# Ardumouse_test.net
KiCad netlist of a schematic drawn in EAGLE
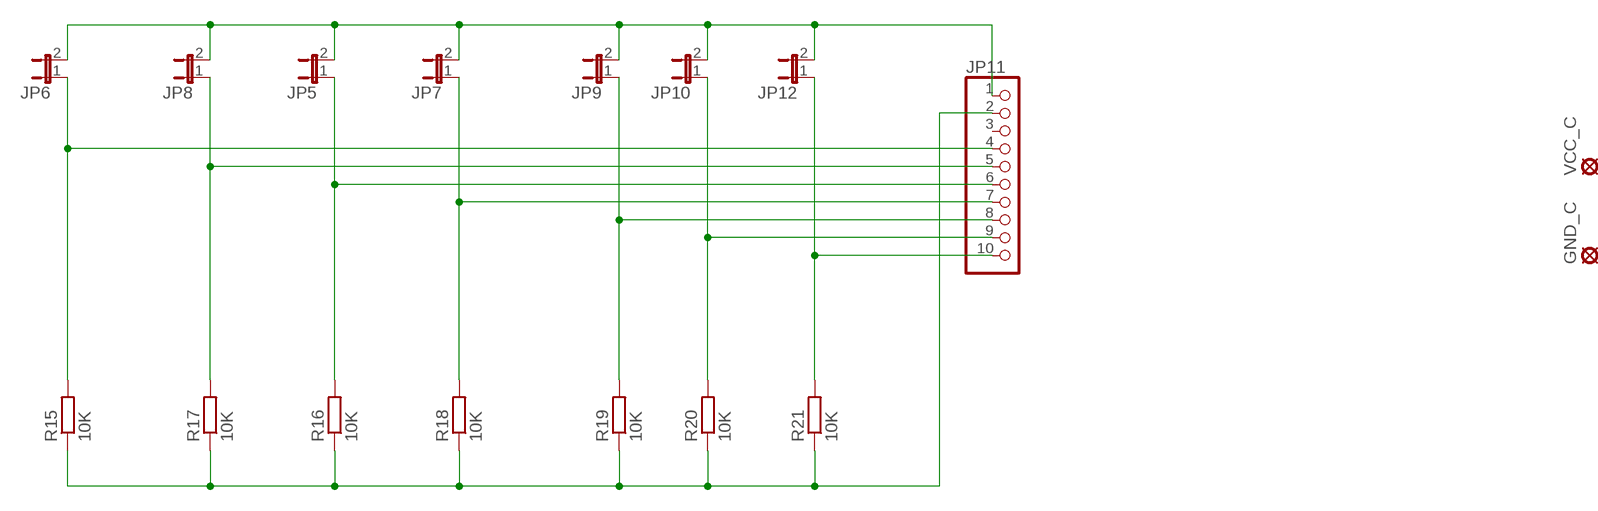
[diagram p0: schematic, sheet 1, part 1 of 2]
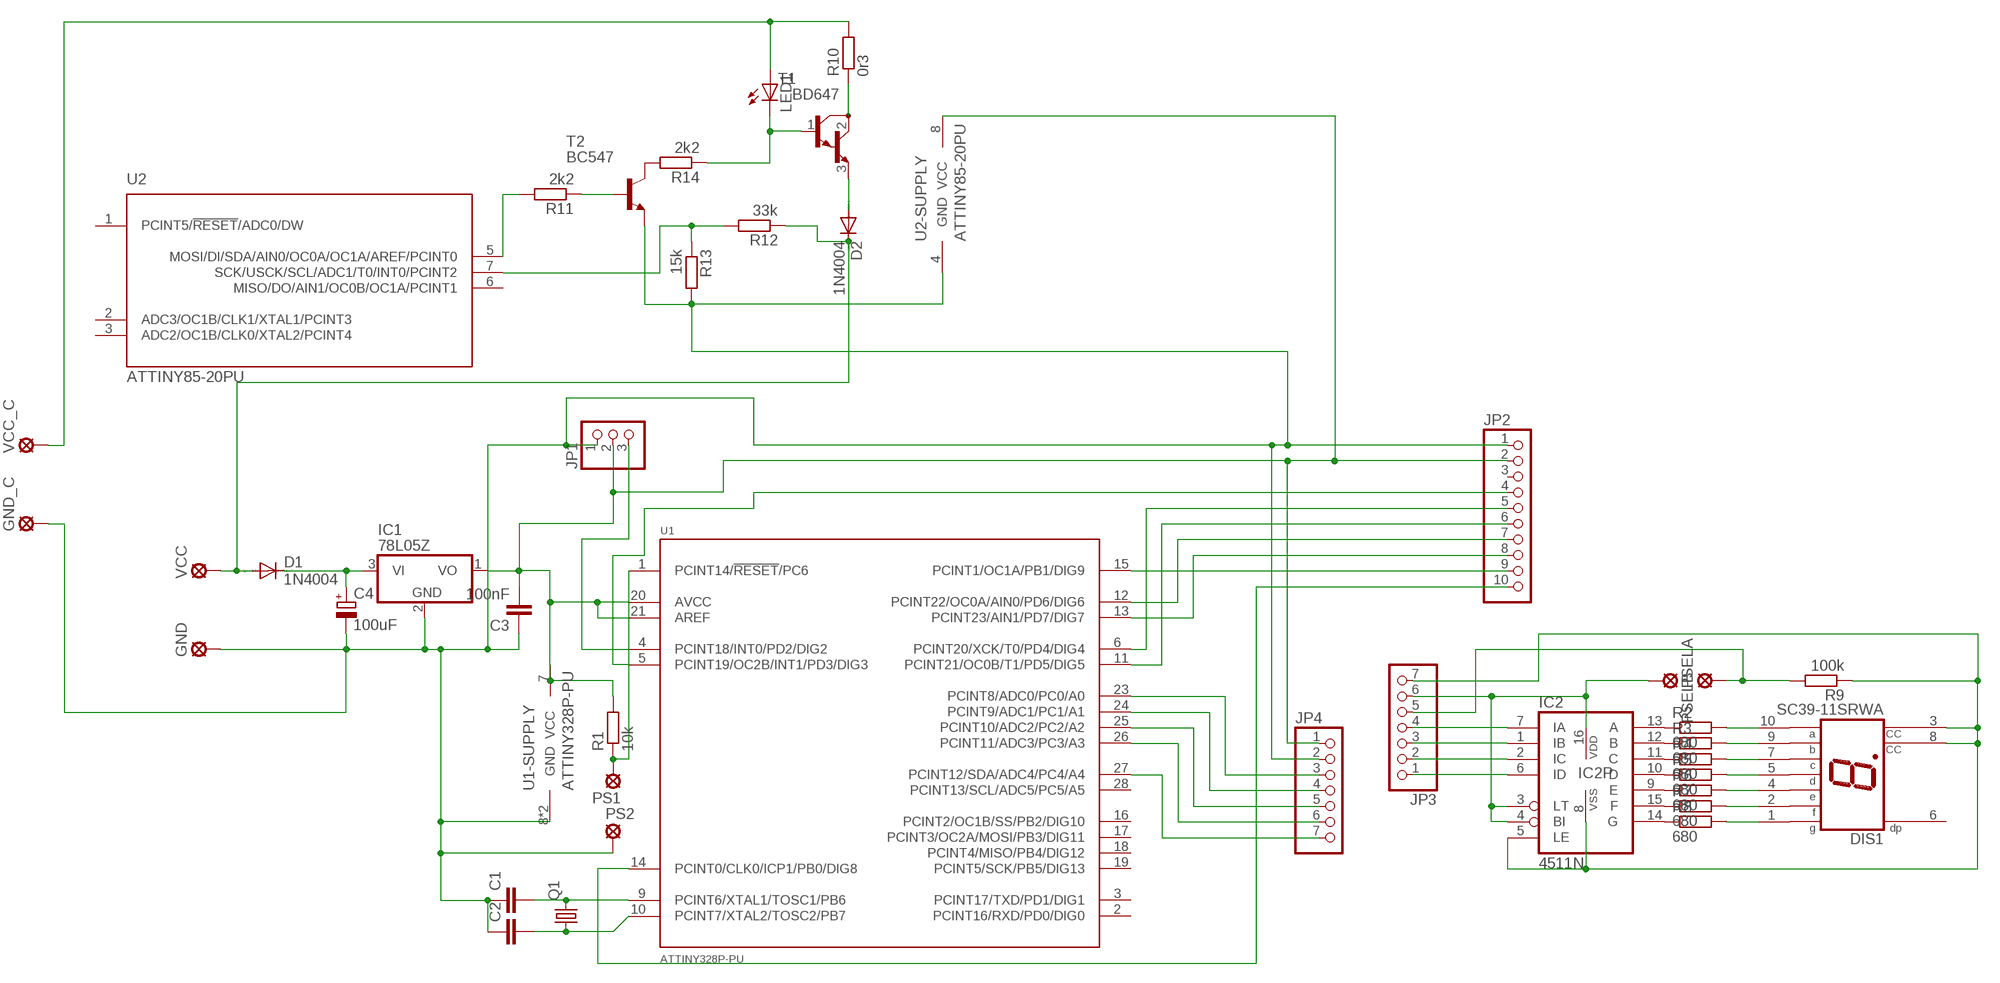
[diagram p1: schematic, sheet 1, part 2 of 2]

(export (version "E")
  (design (tool "Eeschema 10.0.6"))
  (components
    (comp (ref "C1")
      (value "C2,5-3")
      (footprint "eagle-import:C2.5-3")
      (libsource (lib "eagle-import") (part "C2,5-3"))
    )
    (comp (ref "C2")
      (value "C2,5-3")
      (footprint "eagle-import:C2.5-3")
      (libsource (lib "eagle-import") (part "C2,5-3"))
    )
    (comp (ref "C3")
      (value "100nF")
      (footprint "eagle-import:C2.5-3")
      (libsource (lib "eagle-import") (part "C2,5-3"))
    )
    (comp (ref "C4")
      (value "100uF")
      (footprint "eagle-import:E3,5-8")
      (libsource (lib "eagle-import") (part "CPOL-EUE3.5-8"))
    )
    (comp (ref "D1")
      (value "1N4004")
      (footprint "eagle-import:DO41-10")
      (libsource (lib "eagle-import") (part "1N4004"))
    )
    (comp (ref "D2")
      (value "1N4004")
      (footprint "eagle-import:DO41-10")
      (libsource (lib "eagle-import") (part "1N4004"))
    )
    (comp (ref "DIS1")
      (value "SC39-11SRWA")
      (footprint "eagle-import:HDSP-E")
      (libsource (lib "eagle-import") (part "SC39-11SRWA"))
    )
    (comp (ref "GND")
      (value "LSP10")
      (footprint "eagle-import:LSP10")
      (libsource (lib "eagle-import") (part "LSP10"))
    )
    (comp (ref "GND_C")
      (value "LSP10")
      (footprint "eagle-import:LSP10")
      (libsource (lib "eagle-import") (part "LSP10"))
    )
    (comp (ref "IC1")
      (value "78L05Z")
      (footprint "eagle-import:TO92")
      (libsource (lib "eagle-import") (part "78ZL05"))
    )
    (comp (ref "IC2")
      (value "4511N")
      (footprint "eagle-import:DIL16")
      (libsource (lib "eagle-import") (part "4511N"))
    )
    (comp (ref "JP1")
      (value "PINHD-1X3")
      (footprint "eagle-import:1X03")
      (libsource (lib "eagle-import") (part "PINHD-1X3"))
    )
    (comp (ref "JP2")
      (value "PINHD-1X10")
      (footprint "eagle-import:1X10")
      (libsource (lib "eagle-import") (part "PINHD-1X10"))
    )
    (comp (ref "JP3")
      (value "PINHD-1X7")
      (footprint "eagle-import:1X07")
      (libsource (lib "eagle-import") (part "PINHD-1X7"))
    )
    (comp (ref "JP4")
      (value "PINHD-1X7")
      (footprint "eagle-import:1X07")
      (libsource (lib "eagle-import") (part "PINHD-1X7"))
    )
    (comp (ref "JP5")
      (value "JP1E")
      (footprint "eagle-import:JP1")
      (libsource (lib "eagle-import") (part "JP1E"))
    )
    (comp (ref "JP6")
      (value "JP1E")
      (footprint "eagle-import:JP1")
      (libsource (lib "eagle-import") (part "JP1E"))
    )
    (comp (ref "JP7")
      (value "JP1E")
      (footprint "eagle-import:JP1")
      (libsource (lib "eagle-import") (part "JP1E"))
    )
    (comp (ref "JP8")
      (value "JP1E")
      (footprint "eagle-import:JP1")
      (libsource (lib "eagle-import") (part "JP1E"))
    )
    (comp (ref "JP9")
      (value "JP1E")
      (footprint "eagle-import:JP1")
      (libsource (lib "eagle-import") (part "JP1E"))
    )
    (comp (ref "JP10")
      (value "JP1E")
      (footprint "eagle-import:JP1")
      (libsource (lib "eagle-import") (part "JP1E"))
    )
    (comp (ref "JP11")
      (value "PINHD-1X10")
      (footprint "eagle-import:1X10")
      (libsource (lib "eagle-import") (part "PINHD-1X10"))
    )
    (comp (ref "JP12")
      (value "JP1E")
      (footprint "eagle-import:JP1")
      (libsource (lib "eagle-import") (part "JP1E"))
    )
    (comp (ref "LED1")
      (value "LED5MM")
      (footprint "eagle-import:LED5MM")
      (libsource (lib "eagle-import") (part "LED5MM"))
    )
    (comp (ref "PS1")
      (value "LSP10")
      (footprint "eagle-import:LSP10")
      (libsource (lib "eagle-import") (part "LSP10"))
    )
    (comp (ref "PS2")
      (value "LSP10")
      (footprint "eagle-import:LSP10")
      (libsource (lib "eagle-import") (part "LSP10"))
    )
    (comp (ref "PSELA")
      (value "LSP10")
      (footprint "eagle-import:LSP10")
      (libsource (lib "eagle-import") (part "LSP10"))
    )
    (comp (ref "PSELB")
      (value "LSP10")
      (footprint "eagle-import:LSP10")
      (libsource (lib "eagle-import") (part "LSP10"))
    )
    (comp (ref "Q1")
      (value "CRYSTALHC49S")
      (footprint "eagle-import:HC49_S")
      (libsource (lib "eagle-import") (part "CRYSTALHC49S"))
    )
    (comp (ref "R1")
      (value "10k")
      (footprint "eagle-import:0204_7")
      (libsource (lib "eagle-import") (part "resistor_R-EU_0204/7"))
    )
    (comp (ref "R2")
      (value "680")
      (footprint "eagle-import:0204_7")
      (libsource (lib "eagle-import") (part "resistor_R-EU_0204/7"))
    )
    (comp (ref "R3")
      (value "680")
      (footprint "eagle-import:0204_7")
      (libsource (lib "eagle-import") (part "resistor_R-EU_0204/7"))
    )
    (comp (ref "R4")
      (value "680")
      (footprint "eagle-import:0204_7")
      (libsource (lib "eagle-import") (part "resistor_R-EU_0204/7"))
    )
    (comp (ref "R5")
      (value "680")
      (footprint "eagle-import:0204_7")
      (libsource (lib "eagle-import") (part "resistor_R-EU_0204/7"))
    )
    (comp (ref "R6")
      (value "680")
      (footprint "eagle-import:0204_7")
      (libsource (lib "eagle-import") (part "resistor_R-EU_0204/7"))
    )
    (comp (ref "R7")
      (value "680")
      (footprint "eagle-import:0204_7")
      (libsource (lib "eagle-import") (part "resistor_R-EU_0204/7"))
    )
    (comp (ref "R8")
      (value "680")
      (footprint "eagle-import:0204_7")
      (libsource (lib "eagle-import") (part "resistor_R-EU_0204/7"))
    )
    (comp (ref "R9")
      (value "100k")
      (footprint "eagle-import:0204_7")
      (libsource (lib "eagle-import") (part "R-EU_0204/7"))
    )
    (comp (ref "R10")
      (value "0r3")
      (footprint "eagle-import:0204_7")
      (libsource (lib "eagle-import") (part "resistor_R-EU_0204/7"))
    )
    (comp (ref "R11")
      (value "2k2")
      (footprint "eagle-import:0204_7")
      (libsource (lib "eagle-import") (part "resistor_R-EU_0204/7"))
    )
    (comp (ref "R12")
      (value "33k")
      (footprint "eagle-import:0204_7")
      (libsource (lib "eagle-import") (part "resistor_R-EU_0204/7"))
    )
    (comp (ref "R13")
      (value "15k")
      (footprint "eagle-import:0204_7")
      (libsource (lib "eagle-import") (part "resistor_R-EU_0204/7"))
    )
    (comp (ref "R14")
      (value "2k2")
      (footprint "eagle-import:0204_7")
      (libsource (lib "eagle-import") (part "resistor_R-EU_0204/7"))
    )
    (comp (ref "R15")
      (value "10K")
      (footprint "eagle-import:0204_7")
      (libsource (lib "eagle-import") (part "R-EU_0204/7"))
    )
    (comp (ref "R16")
      (value "10K")
      (footprint "eagle-import:0204_7")
      (libsource (lib "eagle-import") (part "R-EU_0204/7"))
    )
    (comp (ref "R17")
      (value "10K")
      (footprint "eagle-import:0204_7")
      (libsource (lib "eagle-import") (part "R-EU_0204/7"))
    )
    (comp (ref "R18")
      (value "10K")
      (footprint "eagle-import:0204_7")
      (libsource (lib "eagle-import") (part "R-EU_0204/7"))
    )
    (comp (ref "R19")
      (value "10K")
      (footprint "eagle-import:0204_7")
      (libsource (lib "eagle-import") (part "R-EU_0204/7"))
    )
    (comp (ref "R20")
      (value "10K")
      (footprint "eagle-import:0204_7")
      (libsource (lib "eagle-import") (part "R-EU_0204/7"))
    )
    (comp (ref "R21")
      (value "10K")
      (footprint "eagle-import:0204_7")
      (libsource (lib "eagle-import") (part "R-EU_0204/7"))
    )
    (comp (ref "T1")
      (value "BD647")
      (footprint "eagle-import:TO220")
      (libsource (lib "eagle-import") (part "BD647"))
    )
    (comp (ref "T2")
      (value "BC547")
      (footprint "eagle-import:TO92")
      (libsource (lib "eagle-import") (part "BC547"))
    )
    (comp (ref "U1")
      (value "ATTINY328P-PU")
      (footprint "eagle-import:DIP-28")
      (fields (field (name "MANUFACTURER") "Atmel") (field (name "PART_NUMBER") "ATMEGA328P-PU"))
      (libsource (lib "eagle-import") (part "ATTINY8P-?PU32"))
    )
    (comp (ref "U2")
      (value "ATTINY85-20PU")
      (footprint "eagle-import:DIP-8")
      (fields (field (name "MANUFACTURER") "Atmel"))
      (libsource (lib "eagle-import") (part "ATTINY5-?20PU8"))
    )
    (comp (ref "VCC")
      (value "LSP10")
      (footprint "eagle-import:LSP10")
      (libsource (lib "eagle-import") (part "LSP10"))
    )
    (comp (ref "VCC_C")
      (value "LSP10")
      (footprint "eagle-import:LSP10")
      (libsource (lib "eagle-import") (part "LSP10"))
    )
  )
  (nets
    (net (code "1") (name "Net-(D1-PadA)") (class "Default")
      (node (ref "D1") (pin "A") (pinfunction "A_A") (pintype "passive"))
      (node (ref "D2") (pin "C") (pinfunction "C_C") (pintype "passive"))
      (node (ref "R12") (pin "1") (pinfunction "1_1") (pintype "passive"))
      (node (ref "VCC") (pin "MP") (pinfunction "MP_MP") (pintype "passive"))
    )
    (net (code "2") (name "Net-(DIS1-A)") (class "Default")
      (node (ref "DIS1") (pin "10") (pinfunction "A_10") (pintype "passive"))
      (node (ref "R2") (pin "2") (pinfunction "2_2") (pintype "passive"))
    )
    (net (code "3") (name "Net-(DIS1-B)") (class "Default")
      (node (ref "DIS1") (pin "9") (pinfunction "B_9") (pintype "passive"))
      (node (ref "R3") (pin "2") (pinfunction "2_2") (pintype "passive"))
    )
    (net (code "4") (name "Net-(DIS1-C)") (class "Default")
      (node (ref "DIS1") (pin "7") (pinfunction "C_7") (pintype "passive"))
      (node (ref "R4") (pin "2") (pinfunction "2_2") (pintype "passive"))
    )
    (net (code "5") (name "Net-(DIS1-D)") (class "Default")
      (node (ref "DIS1") (pin "5") (pinfunction "D_5") (pintype "passive"))
      (node (ref "R5") (pin "2") (pinfunction "2_2") (pintype "passive"))
    )
    (net (code "6") (name "Net-(DIS1-E)") (class "Default")
      (node (ref "DIS1") (pin "4") (pinfunction "E_4") (pintype "passive"))
      (node (ref "R6") (pin "2") (pinfunction "2_2") (pintype "passive"))
    )
    (net (code "7") (name "Net-(DIS1-F)") (class "Default")
      (node (ref "DIS1") (pin "2") (pinfunction "F_2") (pintype "passive"))
      (node (ref "R7") (pin "2") (pinfunction "2_2") (pintype "passive"))
    )
    (net (code "8") (name "Net-(DIS1-G)") (class "Default")
      (node (ref "DIS1") (pin "1") (pinfunction "G_1") (pintype "passive"))
      (node (ref "R8") (pin "2") (pinfunction "2_2") (pintype "passive"))
    )
    (net (code "9") (name "Net-(IC1-GND)") (class "Default")
      (node (ref "C1") (pin "1") (pinfunction "1_1") (pintype "passive"))
      (node (ref "C2") (pin "1") (pinfunction "1_1") (pintype "passive"))
      (node (ref "C3") (pin "1") (pinfunction "1_1") (pintype "passive"))
      (node (ref "C4") (pin "-") (pinfunction "-_-") (pintype "passive"))
      (node (ref "GND") (pin "MP") (pinfunction "MP_MP") (pintype "passive"))
      (node (ref "GND_C") (pin "MP") (pinfunction "MP_MP") (pintype "passive"))
      (node (ref "IC1") (pin "2") (pinfunction "GND_2") (pintype "passive"))
      (node (ref "JP1") (pin "1") (pinfunction "1_1") (pintype "passive"))
      (node (ref "JP2") (pin "1") (pinfunction "1_1") (pintype "passive"))
      (node (ref "JP4") (pin "2") (pinfunction "2_2") (pintype "passive"))
      (node (ref "PS2") (pin "MP") (pinfunction "MP_MP") (pintype "passive"))
      (node (ref "R13") (pin "2") (pinfunction "2_2") (pintype "passive"))
      (node (ref "T2") (pin "1") (pinfunction "E_1") (pintype "passive"))
      (node (ref "U1") (pin "22") (pinfunction "GND_22") (pintype "power_in"))
      (node (ref "U1") (pin "8") (pinfunction "GND_8") (pintype "power_in"))
      (node (ref "U2") (pin "4") (pinfunction "GND_4") (pintype "power_in"))
    )
    (net (code "10") (name "Net-(IC1-VI)") (class "Default")
      (node (ref "C4") (pin "+") (pinfunction "+_+") (pintype "passive"))
      (node (ref "D1") (pin "C") (pinfunction "C_C") (pintype "passive"))
      (node (ref "IC1") (pin "3") (pinfunction "VI_3") (pintype "input"))
    )
    (net (code "11") (name "Net-(IC1-VO)") (class "Default")
      (node (ref "C3") (pin "2") (pinfunction "2_2") (pintype "passive"))
      (node (ref "IC1") (pin "1") (pinfunction "VO_1") (pintype "passive"))
      (node (ref "JP1") (pin "2") (pinfunction "2_2") (pintype "passive"))
      (node (ref "JP2") (pin "2") (pinfunction "2_2") (pintype "passive"))
      (node (ref "JP4") (pin "1") (pinfunction "1_1") (pintype "passive"))
      (node (ref "R1") (pin "2") (pinfunction "2_2") (pintype "passive"))
      (node (ref "U1") (pin "20") (pinfunction "AVCC_20") (pintype "bidirectional"))
      (node (ref "U1") (pin "21") (pinfunction "AREF_21") (pintype "bidirectional"))
      (node (ref "U1") (pin "7") (pinfunction "VCC_7") (pintype "power_in"))
      (node (ref "U2") (pin "8") (pinfunction "VCC_8") (pintype "power_in"))
    )
    (net (code "12") (name "Net-(IC2A-A)") (class "Default")
      (node (ref "IC2") (pin "13") (pinfunction "A_13") (pintype "output"))
      (node (ref "R2") (pin "1") (pinfunction "1_1") (pintype "passive"))
    )
    (net (code "13") (name "Net-(IC2A-B)") (class "Default")
      (node (ref "IC2") (pin "12") (pinfunction "B_12") (pintype "output"))
      (node (ref "R3") (pin "1") (pinfunction "1_1") (pintype "passive"))
    )
    (net (code "14") (name "Net-(IC2A-BI)") (class "Default")
      (node (ref "IC2") (pin "16") (pinfunction "VDD_16") (pintype "power_in"))
      (node (ref "IC2") (pin "3") (pinfunction "LT_3") (pintype "input"))
      (node (ref "IC2") (pin "4") (pinfunction "BI_4") (pintype "input"))
      (node (ref "JP3") (pin "6") (pinfunction "6_6") (pintype "passive"))
      (node (ref "PSELB") (pin "MP") (pinfunction "MP_MP") (pintype "passive"))
    )
    (net (code "15") (name "Net-(IC2A-C)") (class "Default")
      (node (ref "IC2") (pin "11") (pinfunction "C_11") (pintype "output"))
      (node (ref "R4") (pin "1") (pinfunction "1_1") (pintype "passive"))
    )
    (net (code "16") (name "Net-(IC2A-D)") (class "Default")
      (node (ref "IC2") (pin "10") (pinfunction "D_10") (pintype "output"))
      (node (ref "R5") (pin "1") (pinfunction "1_1") (pintype "passive"))
    )
    (net (code "17") (name "Net-(IC2A-E)") (class "Default")
      (node (ref "IC2") (pin "9") (pinfunction "E_9") (pintype "output"))
      (node (ref "R6") (pin "1") (pinfunction "1_1") (pintype "passive"))
    )
    (net (code "18") (name "Net-(IC2A-F)") (class "Default")
      (node (ref "IC2") (pin "15") (pinfunction "F_15") (pintype "output"))
      (node (ref "R7") (pin "1") (pinfunction "1_1") (pintype "passive"))
    )
    (net (code "19") (name "Net-(IC2A-G)") (class "Default")
      (node (ref "IC2") (pin "14") (pinfunction "G_14") (pintype "output"))
      (node (ref "R8") (pin "1") (pinfunction "1_1") (pintype "passive"))
    )
    (net (code "20") (name "Net-(IC2A-IA)") (class "Default")
      (node (ref "IC2") (pin "7") (pinfunction "IA_7") (pintype "input"))
      (node (ref "JP3") (pin "4") (pinfunction "4_4") (pintype "passive"))
    )
    (net (code "21") (name "Net-(IC2A-IB)") (class "Default")
      (node (ref "IC2") (pin "1") (pinfunction "IB_1") (pintype "input"))
      (node (ref "JP3") (pin "3") (pinfunction "3_3") (pintype "passive"))
    )
    (net (code "22") (name "Net-(IC2A-IC)") (class "Default")
      (node (ref "IC2") (pin "2") (pinfunction "IC_2") (pintype "input"))
      (node (ref "JP3") (pin "2") (pinfunction "2_2") (pintype "passive"))
    )
    (net (code "23") (name "Net-(IC2A-ID)") (class "Default")
      (node (ref "IC2") (pin "6") (pinfunction "ID_6") (pintype "input"))
      (node (ref "JP3") (pin "1") (pinfunction "1_1") (pintype "passive"))
    )
    (net (code "24") (name "Net-(IC2A-LE)") (class "Default")
      (node (ref "DIS1") (pin "3") (pinfunction "CC_3") (pintype "passive"))
      (node (ref "DIS1") (pin "8") (pinfunction "CC_8") (pintype "passive"))
      (node (ref "IC2") (pin "5") (pinfunction "LE_5") (pintype "input"))
      (node (ref "IC2") (pin "8") (pinfunction "VSS_8") (pintype "power_in"))
      (node (ref "JP3") (pin "7") (pinfunction "7_7") (pintype "passive"))
      (node (ref "R9") (pin "1") (pinfunction "1_1") (pintype "passive"))
    )
    (net (code "25") (name "Net-(JP3-Pad5)") (class "Default")
      (node (ref "JP3") (pin "5") (pinfunction "5_5") (pintype "passive"))
      (node (ref "PSELA") (pin "MP") (pinfunction "MP_MP") (pintype "passive"))
      (node (ref "R9") (pin "2") (pinfunction "2_2") (pintype "passive"))
    )
    (net (code "26") (name "Net-(JP10-Pad1)") (class "Default")
      (node (ref "JP10") (pin "1") (pinfunction "1_1") (pintype "passive"))
      (node (ref "JP11") (pin "9") (pinfunction "9_9") (pintype "passive"))
      (node (ref "R20") (pin "2") (pinfunction "2_2") (pintype "passive"))
    )
    (net (code "27") (name "Net-(JP10-Pad2)") (class "Default")
      (node (ref "JP10") (pin "2") (pinfunction "2_2") (pintype "passive"))
      (node (ref "JP11") (pin "1") (pinfunction "1_1") (pintype "passive"))
      (node (ref "JP12") (pin "2") (pinfunction "2_2") (pintype "passive"))
      (node (ref "JP5") (pin "2") (pinfunction "2_2") (pintype "passive"))
      (node (ref "JP6") (pin "2") (pinfunction "2_2") (pintype "passive"))
      (node (ref "JP7") (pin "2") (pinfunction "2_2") (pintype "passive"))
      (node (ref "JP8") (pin "2") (pinfunction "2_2") (pintype "passive"))
      (node (ref "JP9") (pin "2") (pinfunction "2_2") (pintype "passive"))
    )
    (net (code "28") (name "Net-(JP11-Pad2)") (class "Default")
      (node (ref "JP11") (pin "2") (pinfunction "2_2") (pintype "passive"))
      (node (ref "R15") (pin "1") (pinfunction "1_1") (pintype "passive"))
      (node (ref "R16") (pin "1") (pinfunction "1_1") (pintype "passive"))
      (node (ref "R17") (pin "1") (pinfunction "1_1") (pintype "passive"))
      (node (ref "R18") (pin "1") (pinfunction "1_1") (pintype "passive"))
      (node (ref "R19") (pin "1") (pinfunction "1_1") (pintype "passive"))
      (node (ref "R20") (pin "1") (pinfunction "1_1") (pintype "passive"))
      (node (ref "R21") (pin "1") (pinfunction "1_1") (pintype "passive"))
    )
    (net (code "29") (name "Net-(JP11-Pad4)") (class "Default")
      (node (ref "JP11") (pin "4") (pinfunction "4_4") (pintype "passive"))
      (node (ref "JP6") (pin "1") (pinfunction "1_1") (pintype "passive"))
      (node (ref "R15") (pin "2") (pinfunction "2_2") (pintype "passive"))
    )
    (net (code "30") (name "Net-(JP11-Pad5)") (class "Default")
      (node (ref "JP11") (pin "5") (pinfunction "5_5") (pintype "passive"))
      (node (ref "JP8") (pin "1") (pinfunction "1_1") (pintype "passive"))
      (node (ref "R17") (pin "2") (pinfunction "2_2") (pintype "passive"))
    )
    (net (code "31") (name "Net-(JP11-Pad6)") (class "Default")
      (node (ref "JP11") (pin "6") (pinfunction "6_6") (pintype "passive"))
      (node (ref "JP5") (pin "1") (pinfunction "1_1") (pintype "passive"))
      (node (ref "R16") (pin "2") (pinfunction "2_2") (pintype "passive"))
    )
    (net (code "32") (name "Net-(JP11-Pad7)") (class "Default")
      (node (ref "JP11") (pin "7") (pinfunction "7_7") (pintype "passive"))
      (node (ref "JP7") (pin "1") (pinfunction "1_1") (pintype "passive"))
      (node (ref "R18") (pin "2") (pinfunction "2_2") (pintype "passive"))
    )
    (net (code "33") (name "Net-(JP11-Pad8)") (class "Default")
      (node (ref "JP11") (pin "8") (pinfunction "8_8") (pintype "passive"))
      (node (ref "JP9") (pin "1") (pinfunction "1_1") (pintype "passive"))
      (node (ref "R19") (pin "2") (pinfunction "2_2") (pintype "passive"))
    )
    (net (code "34") (name "Net-(JP11-Pad10)") (class "Default")
      (node (ref "JP11") (pin "10") (pinfunction "10_10") (pintype "passive"))
      (node (ref "JP12") (pin "1") (pinfunction "1_1") (pintype "passive"))
      (node (ref "R21") (pin "2") (pinfunction "2_2") (pintype "passive"))
    )
    (net (code "35") (name "Net-(LED1-C)") (class "Default")
      (node (ref "LED1") (pin "K") (pinfunction "C_K") (pintype "passive"))
      (node (ref "R14") (pin "1") (pinfunction "1_1") (pintype "passive"))
      (node (ref "T1") (pin "1") (pinfunction "B_1") (pintype "passive"))
    )
    (net (code "36") (name "Net-(LED1-PadA)") (class "Default")
      (node (ref "LED1") (pin "A") (pinfunction "A_A") (pintype "passive"))
      (node (ref "R10") (pin "2") (pinfunction "2_2") (pintype "passive"))
      (node (ref "VCC_C") (pin "MP") (pinfunction "MP_MP") (pintype "passive"))
    )
    (net (code "37") (name "Net-(T1-C)") (class "Default")
      (node (ref "R10") (pin "1") (pinfunction "1_1") (pintype "passive"))
      (node (ref "T1") (pin "2") (pinfunction "C_2") (pintype "passive"))
    )
    (net (code "38") (name "Net-(T1-E)") (class "Default")
      (node (ref "D2") (pin "A") (pinfunction "A_A") (pintype "passive"))
      (node (ref "T1") (pin "3") (pinfunction "E_3") (pintype "passive"))
    )
    (net (code "39") (name "Net-(T2-B)") (class "Default")
      (node (ref "R11") (pin "1") (pinfunction "1_1") (pintype "passive"))
      (node (ref "T2") (pin "2") (pinfunction "B_2") (pintype "passive"))
    )
    (net (code "40") (name "Net-(T2-C)") (class "Default")
      (node (ref "R14") (pin "2") (pinfunction "2_2") (pintype "passive"))
      (node (ref "T2") (pin "3") (pinfunction "C_3") (pintype "passive"))
    )
    (net (code "41") (name "Net-(U1B-PCINT0{slash}CLK0{slash}ICP1{slash}PB0{slash}DIG8)") (class "Default")
      (node (ref "JP2") (pin "10") (pinfunction "10_10") (pintype "passive"))
      (node (ref "U1") (pin "14") (pinfunction "PCINT0/CLK0/ICP1/PB0/DIG8_14") (pintype "bidirectional"))
    )
    (net (code "42") (name "Net-(U1B-PCINT1{slash}OC1A{slash}PB1{slash}DIG9)") (class "Default")
      (node (ref "JP2") (pin "9") (pinfunction "9_9") (pintype "passive"))
      (node (ref "U1") (pin "15") (pinfunction "PCINT1/OC1A/PB1/DIG9_15") (pintype "bidirectional"))
    )
    (net (code "43") (name "Net-(U1B-PCINT6{slash}XTAL1{slash}TOSC1{slash}PB6)") (class "Default")
      (node (ref "C1") (pin "2") (pinfunction "2_2") (pintype "passive"))
      (node (ref "Q1") (pin "2") (pinfunction "2_2") (pintype "passive"))
      (node (ref "U1") (pin "9") (pinfunction "PCINT6/XTAL1/TOSC1/PB6_9") (pintype "bidirectional"))
    )
    (net (code "44") (name "Net-(U1B-PCINT7{slash}XTAL2{slash}TOSC2{slash}PB7)") (class "Default")
      (node (ref "C2") (pin "2") (pinfunction "2_2") (pintype "passive"))
      (node (ref "Q1") (pin "1") (pinfunction "1_1") (pintype "passive"))
      (node (ref "U1") (pin "10") (pinfunction "PCINT7/XTAL2/TOSC2/PB7_10") (pintype "bidirectional"))
    )
    (net (code "45") (name "Net-(U1B-PCINT8{slash}ADC0{slash}PC0{slash}A0)") (class "Default")
      (node (ref "JP4") (pin "3") (pinfunction "3_3") (pintype "passive"))
      (node (ref "U1") (pin "23") (pinfunction "PCINT8/ADC0/PC0/A0_23") (pintype "bidirectional"))
    )
    (net (code "46") (name "Net-(U1B-PCINT9{slash}ADC1{slash}PC1{slash}A1)") (class "Default")
      (node (ref "JP4") (pin "4") (pinfunction "4_4") (pintype "passive"))
      (node (ref "U1") (pin "24") (pinfunction "PCINT9/ADC1/PC1/A1_24") (pintype "bidirectional"))
    )
    (net (code "47") (name "Net-(U1B-PCINT10{slash}ADC2{slash}PC2{slash}A2)") (class "Default")
      (node (ref "JP4") (pin "5") (pinfunction "5_5") (pintype "passive"))
      (node (ref "U1") (pin "25") (pinfunction "PCINT10/ADC2/PC2/A2_25") (pintype "bidirectional"))
    )
    (net (code "48") (name "Net-(U1B-PCINT11{slash}ADC3{slash}PC3{slash}A3)") (class "Default")
      (node (ref "JP4") (pin "6") (pinfunction "6_6") (pintype "passive"))
      (node (ref "U1") (pin "26") (pinfunction "PCINT11/ADC3/PC3/A3_26") (pintype "bidirectional"))
    )
    (net (code "49") (name "Net-(U1B-PCINT12{slash}SDA{slash}ADC4{slash}PC4{slash}A4)") (class "Default")
      (node (ref "JP4") (pin "7") (pinfunction "7_7") (pintype "passive"))
      (node (ref "U1") (pin "27") (pinfunction "PCINT12/SDA/ADC4/PC4/A4_27") (pintype "bidirectional"))
    )
    (net (code "50") (name "Net-(U1B-PCINT14{slash}~{RESET}{slash}PC6)") (class "Default")
      (node (ref "PS1") (pin "MP") (pinfunction "MP_MP") (pintype "passive"))
      (node (ref "R1") (pin "1") (pinfunction "1_1") (pintype "passive"))
      (node (ref "U1") (pin "1") (pinfunction "PCINT14/~{RESET}/PC6_1") (pintype "bidirectional"))
    )
    (net (code "51") (name "Net-(U1B-PCINT18{slash}INT0{slash}PD2{slash}DIG2)") (class "Default")
      (node (ref "JP1") (pin "3") (pinfunction "3_3") (pintype "passive"))
      (node (ref "U1") (pin "4") (pinfunction "PCINT18/INT0/PD2/DIG2_4") (pintype "bidirectional"))
    )
    (net (code "52") (name "Net-(U1B-PCINT19{slash}OC2B{slash}INT1{slash}PD3{slash}DIG3)") (class "Default")
      (node (ref "JP2") (pin "4") (pinfunction "4_4") (pintype "passive"))
      (node (ref "U1") (pin "5") (pinfunction "PCINT19/OC2B/INT1/PD3/DIG3_5") (pintype "bidirectional"))
    )
    (net (code "53") (name "Net-(U1B-PCINT20{slash}XCK{slash}T0{slash}PD4{slash}DIG4)") (class "Default")
      (node (ref "JP2") (pin "5") (pinfunction "5_5") (pintype "passive"))
      (node (ref "U1") (pin "6") (pinfunction "PCINT20/XCK/T0/PD4/DIG4_6") (pintype "bidirectional"))
    )
    (net (code "54") (name "Net-(U1B-PCINT21{slash}OC0B{slash}T1{slash}PD5{slash}DIG5)") (class "Default")
      (node (ref "JP2") (pin "6") (pinfunction "6_6") (pintype "passive"))
      (node (ref "U1") (pin "11") (pinfunction "PCINT21/OC0B/T1/PD5/DIG5_11") (pintype "bidirectional"))
    )
    (net (code "55") (name "Net-(U1B-PCINT22{slash}OC0A{slash}AIN0{slash}PD6{slash}DIG6)") (class "Default")
      (node (ref "JP2") (pin "7") (pinfunction "7_7") (pintype "passive"))
      (node (ref "U1") (pin "12") (pinfunction "PCINT22/OC0A/AIN0/PD6/DIG6_12") (pintype "bidirectional"))
    )
    (net (code "56") (name "Net-(U1B-PCINT23{slash}AIN1{slash}PD7{slash}DIG7)") (class "Default")
      (node (ref "JP2") (pin "8") (pinfunction "8_8") (pintype "passive"))
      (node (ref "U1") (pin "13") (pinfunction "PCINT23/AIN1/PD7/DIG7_13") (pintype "bidirectional"))
    )
    (net (code "57") (name "Net-(U2B-MOSI{slash}DI{slash}SDA{slash}AIN0{slash}OC0A{slash}OC1A{slash}AREF{slash}PCINT0)") (class "Default")
      (node (ref "R11") (pin "2") (pinfunction "2_2") (pintype "passive"))
      (node (ref "U2") (pin "5") (pinfunction "MOSI/DI/SDA/AIN0/OC0A/OC1A/AREF/PCINT0_5") (pintype "bidirectional"))
    )
    (net (code "58") (name "Net-(U2B-SCK{slash}USCK{slash}SCL{slash}ADC1{slash}T0{slash}INT0{slash}PCINT2)") (class "Default")
      (node (ref "R12") (pin "2") (pinfunction "2_2") (pintype "passive"))
      (node (ref "R13") (pin "1") (pinfunction "1_1") (pintype "passive"))
      (node (ref "U2") (pin "7") (pinfunction "SCK/USCK/SCL/ADC1/T0/INT0/PCINT2_7") (pintype "bidirectional"))
    )
    (net (code "59") (name "unconnected-(DIS1-DP-Pad6)") (class "Default")
      (node (ref "DIS1") (pin "6") (pinfunction "DP_6") (pintype "passive"))
    )
    (net (code "60") (name "unconnected-(JP2-Pad3)") (class "Default")
      (node (ref "JP2") (pin "3") (pinfunction "3_3") (pintype "passive"))
    )
    (net (code "61") (name "unconnected-(JP11-Pad3)") (class "Default")
      (node (ref "JP11") (pin "3") (pinfunction "3_3") (pintype "passive"))
    )
    (net (code "62") (name "unconnected-(U1B-PCINT2{slash}OC1B{slash}SS{slash}PB2{slash}DIG10-Pad16)") (class "Default")
      (node (ref "U1") (pin "16") (pinfunction "PCINT2/OC1B/SS/PB2/DIG10_16") (pintype "bidirectional"))
    )
    (net (code "63") (name "unconnected-(U1B-PCINT3{slash}OC2A{slash}MOSI{slash}PB3{slash}DIG11-Pad17)") (class "Default")
      (node (ref "U1") (pin "17") (pinfunction "PCINT3/OC2A/MOSI/PB3/DIG11_17") (pintype "bidirectional"))
    )
    (net (code "64") (name "unconnected-(U1B-PCINT4{slash}MISO{slash}PB4{slash}DIG12-Pad18)") (class "Default")
      (node (ref "U1") (pin "18") (pinfunction "PCINT4/MISO/PB4/DIG12_18") (pintype "bidirectional"))
    )
    (net (code "65") (name "unconnected-(U1B-PCINT5{slash}SCK{slash}PB5{slash}DIG13-Pad19)") (class "Default")
      (node (ref "U1") (pin "19") (pinfunction "PCINT5/SCK/PB5/DIG13_19") (pintype "bidirectional"))
    )
    (net (code "66") (name "unconnected-(U1B-PCINT13{slash}SCL{slash}ADC5{slash}PC5{slash}A5-Pad28)") (class "Default")
      (node (ref "U1") (pin "28") (pinfunction "PCINT13/SCL/ADC5/PC5/A5_28") (pintype "bidirectional"))
    )
    (net (code "67") (name "unconnected-(U1B-PCINT16{slash}RXD{slash}PD0{slash}DIG0-Pad2)") (class "Default")
      (node (ref "U1") (pin "2") (pinfunction "PCINT16/RXD/PD0/DIG0_2") (pintype "bidirectional"))
    )
    (net (code "68") (name "unconnected-(U1B-PCINT17{slash}TXD{slash}PD1{slash}DIG1-Pad3)") (class "Default")
      (node (ref "U1") (pin "3") (pinfunction "PCINT17/TXD/PD1/DIG1_3") (pintype "bidirectional"))
    )
    (net (code "69") (name "unconnected-(U2B-ADC2{slash}OC1B{slash}CLK0{slash}XTAL2{slash}PCINT4-Pad3)") (class "Default")
      (node (ref "U2") (pin "3") (pinfunction "ADC2/OC1B/CLK0/XTAL2/PCINT4_3") (pintype "bidirectional"))
    )
    (net (code "70") (name "unconnected-(U2B-ADC3{slash}OC1B{slash}CLK1{slash}XTAL1{slash}PCINT3-Pad2)") (class "Default")
      (node (ref "U2") (pin "2") (pinfunction "ADC3/OC1B/CLK1/XTAL1/PCINT3_2") (pintype "bidirectional"))
    )
    (net (code "71") (name "unconnected-(U2B-MISO{slash}DO{slash}AIN1{slash}OC0B{slash}OC1A{slash}PCINT1-Pad6)") (class "Default")
      (node (ref "U2") (pin "6") (pinfunction "MISO/DO/AIN1/OC0B/OC1A/PCINT1_6") (pintype "bidirectional"))
    )
    (net (code "72") (name "unconnected-(U2B-PCINT5{slash}~{RESET}{slash}ADC0{slash}DW-Pad1)") (class "Default")
      (node (ref "U2") (pin "1") (pinfunction "PCINT5/~{RESET}/ADC0/DW_1") (pintype "bidirectional"))
    )
  )
)
